# USB.net
KiCad netlist of a schematic drawn in Altium Designer
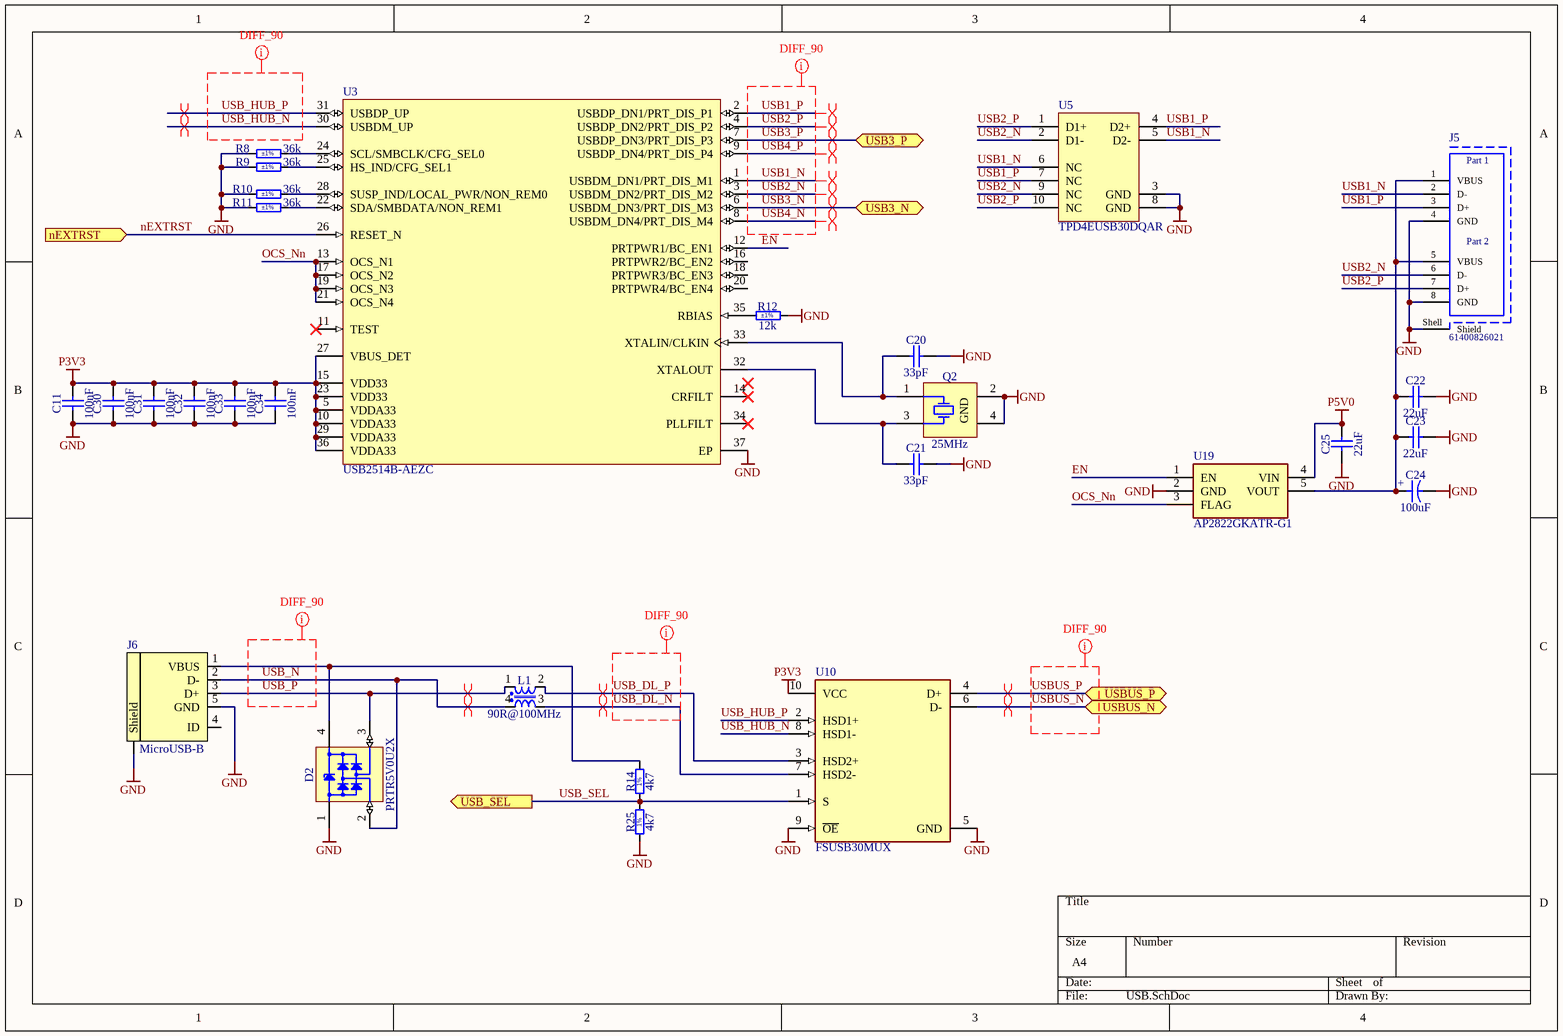
[diagram p0: USB.SchDoc]

(export (version "E")
  (design (tool "Eeschema 10.0.6"))
  (components
    (comp (ref "C11")
      (value "100nF")
      (footprint "CAPC1005X55N")
      (description "Non-polarised capacitor")
      (fields
        (field (name "PART NUMBER") "CC0402_100NF_16V_10%_X5R")
        (field (name "VOLTAGE") "16V")
        (field (name "AUTHOR") "CERN DEM JLC")
      )
      (libsource (lib "Capacitors") (part "Capacitor - non polarized"))
    )
    (comp (ref "C20")
      (value "33pF")
      (footprint "CAPC1005X55N")
      (description "Non-polarised capacitor")
      (fields
        (field (name "PART NUMBER") "CC0402_33PF_50V_5%_C0G")
        (field (name "VOLTAGE") "50V")
        (field (name "AUTHOR") "CERN DEM JLC")
      )
      (libsource (lib "Capacitors") (part "Capacitor - non polarized"))
    )
    (comp (ref "C21")
      (value "33pF")
      (footprint "CAPC1005X55N")
      (description "Non-polarised capacitor")
      (fields
        (field (name "PART NUMBER") "CC0402_33PF_50V_5%_C0G")
        (field (name "VOLTAGE") "50V")
        (field (name "AUTHOR") "CERN DEM JLC")
      )
      (libsource (lib "Capacitors") (part "Capacitor - non polarized"))
    )
    (comp (ref "C22")
      (value "22uF")
      (footprint "CAPC2012X135N")
      (description "Non-polarised capacitor")
      (fields
        (field (name "PART NUMBER") "CC0805_22UF_10V_+80%-20%_Y5V")
        (field (name "VOLTAGE") "10V")
        (field (name "AUTHOR") "CERN DEM JLC")
      )
      (libsource (lib "Capacitors") (part "Capacitor - non polarized"))
    )
    (comp (ref "C23")
      (value "22uF")
      (footprint "CAPC2012X135N")
      (description "Non-polarised capacitor")
      (fields
        (field (name "PART NUMBER") "CC0805_22UF_10V_+80%-20%_Y5V")
        (field (name "VOLTAGE") "10V")
        (field (name "AUTHOR") "CERN DEM JLC")
      )
      (libsource (lib "Capacitors") (part "Capacitor - non polarized"))
    )
    (comp (ref "C24")
      (value "100uF")
      (footprint "CAPMP3216X180N")
      (description "Polarised capacitor")
      (fields
        (field (name "PART NUMBER") "CTE3216-18_100UF_6.3V_20%_ESR0500_AVX_TLJ")
        (field (name "VOLTAGE") "6.3V")
        (field (name "AUTHOR") "CERN DEM JLC")
      )
      (libsource (lib "Capacitors") (part "Capacitor - polarized"))
    )
    (comp (ref "C25")
      (value "22uF")
      (footprint "CAPC2012X135N")
      (description "Non-polarised capacitor")
      (fields
        (field (name "PART NUMBER") "CC0805_22UF_10V_+80%-20%_Y5V")
        (field (name "VOLTAGE") "10V")
        (field (name "AUTHOR") "CERN DEM JLC")
      )
      (libsource (lib "Capacitors") (part "Capacitor - non polarized"))
    )
    (comp (ref "C30")
      (value "100nF")
      (footprint "CAPC1005X55N")
      (description "Non-polarised capacitor")
      (fields
        (field (name "PART NUMBER") "CC0402_100NF_16V_10%_X5R")
        (field (name "VOLTAGE") "16V")
        (field (name "AUTHOR") "CERN DEM JLC")
      )
      (libsource (lib "Capacitors") (part "Capacitor - non polarized"))
    )
    (comp (ref "C31")
      (value "100nF")
      (footprint "CAPC1005X55N")
      (description "Non-polarised capacitor")
      (fields
        (field (name "PART NUMBER") "CC0402_100NF_16V_10%_X5R")
        (field (name "VOLTAGE") "16V")
        (field (name "AUTHOR") "CERN DEM JLC")
      )
      (libsource (lib "Capacitors") (part "Capacitor - non polarized"))
    )
    (comp (ref "C32")
      (value "100nF")
      (footprint "CAPC1005X55N")
      (description "Non-polarised capacitor")
      (fields
        (field (name "PART NUMBER") "CC0402_100NF_16V_10%_X5R")
        (field (name "VOLTAGE") "16V")
        (field (name "AUTHOR") "CERN DEM JLC")
      )
      (libsource (lib "Capacitors") (part "Capacitor - non polarized"))
    )
    (comp (ref "C33")
      (value "100nF")
      (footprint "CAPC1005X55N")
      (description "Non-polarised capacitor")
      (fields
        (field (name "PART NUMBER") "CC0402_100NF_16V_10%_X5R")
        (field (name "VOLTAGE") "16V")
        (field (name "AUTHOR") "CERN DEM JLC")
      )
      (libsource (lib "Capacitors") (part "Capacitor - non polarized"))
    )
    (comp (ref "C34")
      (value "100nF")
      (footprint "CAPC1005X55N")
      (description "Non-polarised capacitor")
      (fields
        (field (name "PART NUMBER") "CC0402_100NF_16V_10%_X5R")
        (field (name "VOLTAGE") "16V")
        (field (name "AUTHOR") "CERN DEM JLC")
      )
      (libsource (lib "Capacitors") (part "Capacitor - non polarized"))
    )
    (comp (ref "D2")
      (value "PRTR5V0U2X")
      (footprint "SOT190P230X110-4N")
      (description "Ultra Low Capacitance Double Rail-to-Rail ESD Protection Diode")
      (fields
        (field (name "VOLTAGE") "5.5V")
        (field (name "MANUFACTURER") "NXP SEMICONDUCTORS")
        (field (name "AUTHOR") "CERN DEM JLC")
      )
      (libsource (lib "ICs And Semiconductors") (part "PRTR5V0U2X"))
    )
    (comp (ref "J5")
      (value "61400826021")
      (footprint "61400826021")
      (description "USB 2.0 Type A Receptacle WR-COM, Stacked Horizontal, THT")
      (fields (field (name "MANUFACTURER") "Wurth Elektronik") (field (name "PUBLISHER") "WurthElektronik"))
      (libsource (lib "Altium Content Vault") (part "WE-USB-8-1SHLD"))
    )
    (comp (ref "J6")
      (value "MicroUSB-B")
      (footprint "USB-Micro-B-RA-SMD-PiP")
      (description "MicroUSB-B-SMT")
      (fields
        (field (name "PART NUMBER") "USB-Micro-B-RA-SMD-PiP")
        (field (name "MANUFACTURER") "Allen Creations Corp.")
        (field (name "PUBLISHER") "Nordic Semiconductor")
      )
      (libsource (lib "pca10028") (part "MiniUSB-AB-SMT"))
    )
    (comp (ref "L1")
      (value "90R@100MHz")
      (footprint "IND_MURATA_DLW21S")
      (description "Inductor Common Mode")
      (fields
        (field (name "PART NUMBER") "IND_MURATA_DLW21SN900SQ2L")
        (field (name "POWER") "330mA")
        (field (name "AUTHOR") "CERN DEM JLC")
      )
      (libsource (lib "Inductors & Transformers") (part "Inductor Common Mode 1Dot-2 4Dot-3"))
    )
    (comp (ref "Q2")
      (value "25MHz")
      (footprint "XTAL_EPSON_TSX-3225")
      (description "Crystal 4 pins 1=XTAL Control 2=GND3=XTAL 4=GND")
      (fields
        (field (name "PART NUMBER") "XTAL_25MHZ_EPSON_TSX-3225 25.0000MF10Z-AC")
        (field (name "MANUFACTURER") "EPSON")
        (field (name "AUTHOR") "CERN DEM JLC")
      )
      (libsource (lib "ICs And Semiconductors") (part "Quartz Crystal 1X 2GND 3X 4GND"))
    )
    (comp (ref "R8")
      (value "36k")
      (footprint "RESC1005X40N")
      (description "Resistor - 1%")
      (fields
        (field (name "TOLERANCE") "±1%")
        (field (name "PART NUMBER") "R0402_36K_1%_0.0625W_100PPM")
        (field (name "POWER") "0.0625W")
        (field (name "AUTHOR") "CERN DEM JLC")
      )
      (libsource (lib "Resistors") (part "Resistor - 1%"))
    )
    (comp (ref "R9")
      (value "36k")
      (footprint "RESC1005X40N")
      (description "Resistor - 1%")
      (fields
        (field (name "TOLERANCE") "±1%")
        (field (name "PART NUMBER") "R0402_36K_1%_0.0625W_100PPM")
        (field (name "POWER") "0.0625W")
        (field (name "AUTHOR") "CERN DEM JLC")
      )
      (libsource (lib "Resistors") (part "Resistor - 1%"))
    )
    (comp (ref "R10")
      (value "36k")
      (footprint "RESC1005X40N")
      (description "Resistor - 1%")
      (fields
        (field (name "TOLERANCE") "±1%")
        (field (name "PART NUMBER") "R0402_36K_1%_0.0625W_100PPM")
        (field (name "POWER") "0.0625W")
        (field (name "AUTHOR") "CERN DEM JLC")
      )
      (libsource (lib "Resistors") (part "Resistor - 1%"))
    )
    (comp (ref "R11")
      (value "36k")
      (footprint "RESC1005X40N")
      (description "Resistor - 1%")
      (fields
        (field (name "TOLERANCE") "±1%")
        (field (name "PART NUMBER") "R0402_36K_1%_0.0625W_100PPM")
        (field (name "POWER") "0.0625W")
        (field (name "AUTHOR") "CERN DEM JLC")
      )
      (libsource (lib "Resistors") (part "Resistor - 1%"))
    )
    (comp (ref "R12")
      (value "12k")
      (footprint "RESC1005X40N")
      (description "Resistor - 1%")
      (fields
        (field (name "TOLERANCE") "±1%")
        (field (name "PART NUMBER") "R0402_12K_1%_0.0625W_100PPM")
        (field (name "POWER") "0.0625W")
        (field (name "AUTHOR") "CERN DEM JLC")
      )
      (libsource (lib "Resistors") (part "Resistor - 1%"))
    )
    (comp (ref "R14")
      (value "4k7")
      (footprint "RESC1005X40N")
      (description "Resistor - 1%")
      (fields
        (field (name "PART NUMBER") "R0402_4K7_1%_0.0625W_100PPM")
        (field (name "POWER") "0.0625W")
        (field (name "AUTHOR") "CERN DEM JLC")
      )
      (libsource (lib "Resistors") (part "Resistor - 1%"))
    )
    (comp (ref "R25")
      (value "4k7")
      (footprint "RESC1005X40N")
      (description "Resistor - 1%")
      (fields
        (field (name "PART NUMBER") "R0402_4K7_1%_0.0625W_100PPM")
        (field (name "POWER") "0.0625W")
        (field (name "AUTHOR") "CERN DEM JLC")
      )
      (libsource (lib "Resistors") (part "Resistor - 1%"))
    )
    (comp (ref "U3")
      (value "USB2514B-AEZC")
      (footprint "MCHP-QFN-36_V")
      (description "USB 2.0 High-Speed Hub Controller, 4 Ports, 3 to 3.6 V, 0 to 85 degC, 36-Pin QFN, RoHS, Tray")
      (fields (field (name "MANUFACTURER") "Microchip"))
      (libsource (lib "Altium Content Vault") (part "MCHP-USB2514B-QFN-36"))
    )
    (comp (ref "U5")
      (value "TPD4EUSB30DQAR")
      (footprint "DQA0010A_V")
      (fields (field (name "MANUFACTURER") "Texas Instruments"))
      (libsource (lib "Altium Content Vault") (part "TI-TPD4EUSB30-SON_DQA-10"))
    )
    (comp (ref "U10")
      (value "FSUSB30MUX")
      (footprint "FP-846AP-IPC_C")
      (description "IC USB SWITCH 2X2 10MSOP")
      (libsource (lib "Altium Content Vault") (part "5ca72592cac3c78d86a160a61081866"))
    )
    (comp (ref "U19")
      (value "AP2822GKATR-G1")
      (footprint "SamacSys:SOT95P282X145-5N")
      (description "Switch")
      (libsource (lib "*") (part "AP2822GKATR-G1"))
    )
  )
  (nets
    (net (code "1") (name "/EN") (class "Default")
      (node (ref "U19") (pin "1") (pinfunction "EN_1") (pintype "passive"))
      (node (ref "U3") (pin "12") (pinfunction "PRTPWR1/BC_EN1_12") (pintype "bidirectional"))
    )
    (net (code "2") (name "/OCS_Nn") (class "Default")
      (node (ref "U19") (pin "3") (pinfunction "FLAG_3") (pintype "passive"))
      (node (ref "U3") (pin "13") (pinfunction "OCS_N1_13") (pintype "input"))
      (node (ref "U3") (pin "17") (pinfunction "OCS_N2_17") (pintype "input"))
      (node (ref "U3") (pin "19") (pinfunction "OCS_N3_19") (pintype "input"))
      (node (ref "U3") (pin "21") (pinfunction "OCS_N4_21") (pintype "input"))
    )
    (net (code "3") (name "/USB1_N") (class "Default")
      (node (ref "J5") (pin "2") (pinfunction "D-_2") (pintype "passive"))
      (node (ref "U3") (pin "1") (pinfunction "USBDM_DN1/PRT_DIS_M1_1") (pintype "bidirectional"))
      (node (ref "U5") (pin "5") (pinfunction "D2-_5") (pintype "passive"))
      (node (ref "U5") (pin "6") (pinfunction "NC_6") (pintype "passive"))
    )
    (net (code "4") (name "/USB1_P") (class "Default")
      (node (ref "J5") (pin "3") (pinfunction "D+_3") (pintype "passive"))
      (node (ref "U3") (pin "2") (pinfunction "USBDP_DN1/PRT_DIS_P1_2") (pintype "bidirectional"))
      (node (ref "U5") (pin "4") (pinfunction "D2+_4") (pintype "passive"))
      (node (ref "U5") (pin "7") (pinfunction "NC_7") (pintype "passive"))
    )
    (net (code "5") (name "/USB2_N") (class "Default")
      (node (ref "J5") (pin "6") (pinfunction "D-_6") (pintype "passive"))
      (node (ref "U3") (pin "3") (pinfunction "USBDM_DN2/PRT_DIS_M2_3") (pintype "bidirectional"))
      (node (ref "U5") (pin "2") (pinfunction "D1-_2") (pintype "passive"))
      (node (ref "U5") (pin "9") (pinfunction "NC_9") (pintype "passive"))
    )
    (net (code "6") (name "/USB2_P") (class "Default")
      (node (ref "J5") (pin "7") (pinfunction "D+_7") (pintype "passive"))
      (node (ref "U3") (pin "4") (pinfunction "USBDP_DN2/PRT_DIS_P2_4") (pintype "bidirectional"))
      (node (ref "U5") (pin "1") (pinfunction "D1+_1") (pintype "passive"))
      (node (ref "U5") (pin "10") (pinfunction "NC_10") (pintype "passive"))
    )
    (net (code "7") (name "/USB3_N") (class "Default")
      (node (ref "U3") (pin "6") (pinfunction "USBDM_DN3/PRT_DIS_M3_6") (pintype "bidirectional"))
    )
    (net (code "8") (name "/USB3_P") (class "Default")
      (node (ref "U3") (pin "7") (pinfunction "USBDP_DN3/PRT_DIS_P3_7") (pintype "bidirectional"))
    )
    (net (code "9") (name "/USB4_N") (class "Default")
      (node (ref "U3") (pin "8") (pinfunction "USBDM_DN4/PRT_DIS_M4_8") (pintype "bidirectional"))
    )
    (net (code "10") (name "/USB4_P") (class "Default")
      (node (ref "U3") (pin "9") (pinfunction "USBDP_DN4/PRT_DIS_P4_9") (pintype "bidirectional"))
    )
    (net (code "11") (name "/USBUS_N") (class "Default")
      (node (ref "U10") (pin "6") (pinfunction "D-_6") (pintype "passive"))
    )
    (net (code "12") (name "/USBUS_P") (class "Default")
      (node (ref "U10") (pin "4") (pinfunction "D+_4") (pintype "passive"))
    )
    (net (code "13") (name "/USB_DL_N") (class "Default")
      (node (ref "L1") (pin "3") (pinfunction "3_3") (pintype "passive"))
      (node (ref "U10") (pin "7") (pinfunction "HSD2-_7") (pintype "input"))
    )
    (net (code "14") (name "/USB_DL_P") (class "Default")
      (node (ref "L1") (pin "2") (pinfunction "2_2") (pintype "passive"))
      (node (ref "U10") (pin "3") (pinfunction "HSD2+_3") (pintype "input"))
    )
    (net (code "15") (name "/USB_HUB_N") (class "Default")
      (node (ref "U10") (pin "8") (pinfunction "HSD1-_8") (pintype "input"))
      (node (ref "U3") (pin "30") (pinfunction "USBDM_UP_30") (pintype "bidirectional"))
    )
    (net (code "16") (name "/USB_HUB_P") (class "Default")
      (node (ref "U10") (pin "2") (pinfunction "HSD1+_2") (pintype "input"))
      (node (ref "U3") (pin "31") (pinfunction "USBDP_UP_31") (pintype "bidirectional"))
    )
    (net (code "17") (name "/USB_N") (class "Default")
      (node (ref "D2") (pin "2") (pinfunction "I/O1_2") (pintype "bidirectional"))
      (node (ref "J6") (pin "2") (pinfunction "D-_2") (pintype "passive"))
      (node (ref "L1") (pin "4") (pinfunction "4_4") (pintype "passive"))
    )
    (net (code "18") (name "/USB_P") (class "Default")
      (node (ref "D2") (pin "3") (pinfunction "I/O2_3") (pintype "bidirectional"))
      (node (ref "J6") (pin "3") (pinfunction "D+_3") (pintype "passive"))
      (node (ref "L1") (pin "1") (pinfunction "1_1") (pintype "passive"))
    )
    (net (code "19") (name "/USB_SEL") (class "Default")
      (node (ref "R14") (pin "1") (pinfunction "1_1") (pintype "passive"))
      (node (ref "R25") (pin "2") (pinfunction "2_2") (pintype "passive"))
      (node (ref "U10") (pin "1") (pinfunction "S_1") (pintype "input"))
    )
    (net (code "20") (name "/nEXTRST") (class "Default")
      (node (ref "U3") (pin "26") (pinfunction "RESET_N_26") (pintype "input"))
    )
    (net (code "21") (name "GND") (class "Default")
      (node (ref "C11") (pin "1") (pinfunction "1_1") (pintype "passive"))
      (node (ref "C20") (pin "2") (pinfunction "2_2") (pintype "passive"))
      (node (ref "C21") (pin "2") (pinfunction "2_2") (pintype "passive"))
      (node (ref "C22") (pin "2") (pinfunction "2_2") (pintype "passive"))
      (node (ref "C23") (pin "2") (pinfunction "2_2") (pintype "passive"))
      (node (ref "C24") (pin "2") (pinfunction "2_2") (pintype "passive"))
      (node (ref "C25") (pin "1") (pinfunction "1_1") (pintype "passive"))
      (node (ref "C30") (pin "1") (pinfunction "1_1") (pintype "passive"))
      (node (ref "C31") (pin "1") (pinfunction "1_1") (pintype "passive"))
      (node (ref "C32") (pin "1") (pinfunction "1_1") (pintype "passive"))
      (node (ref "C33") (pin "1") (pinfunction "1_1") (pintype "passive"))
      (node (ref "C34") (pin "1") (pinfunction "1_1") (pintype "passive"))
      (node (ref "D2") (pin "1") (pinfunction "GND_1") (pintype "power_in"))
      (node (ref "J5") (pin "4") (pinfunction "GND_4") (pintype "passive"))
      (node (ref "J5") (pin "8") (pinfunction "GND_8") (pintype "passive"))
      (node (ref "J5") (pin "Shell") (pinfunction "Shield_Shell") (pintype "passive"))
      (node (ref "J6") (pin "5") (pinfunction "GND_5") (pintype "power_in"))
      (node (ref "J6") (pin "6") (pinfunction "Shield_6") (pintype "power_in"))
      (node (ref "Q2") (pin "2") (pinfunction "GND_2") (pintype "power_in"))
      (node (ref "Q2") (pin "4") (pinfunction "GND_4") (pintype "power_in"))
      (node (ref "R10") (pin "1") (pinfunction "1_1") (pintype "passive"))
      (node (ref "R11") (pin "1") (pinfunction "1_1") (pintype "passive"))
      (node (ref "R12") (pin "2") (pinfunction "2_2") (pintype "passive"))
      (node (ref "R25") (pin "1") (pinfunction "1_1") (pintype "passive"))
      (node (ref "R8") (pin "1") (pinfunction "1_1") (pintype "passive"))
      (node (ref "R9") (pin "1") (pinfunction "1_1") (pintype "passive"))
      (node (ref "U10") (pin "5") (pinfunction "GND_5") (pintype "power_in"))
      (node (ref "U10") (pin "9") (pinfunction "~{OE}_9") (pintype "input"))
      (node (ref "U19") (pin "2") (pinfunction "GND_2") (pintype "passive"))
      (node (ref "U3") (pin "37") (pinfunction "EP_37") (pintype "power_in"))
      (node (ref "U5") (pin "3") (pinfunction "GND_3") (pintype "power_in"))
      (node (ref "U5") (pin "8") (pinfunction "GND_8") (pintype "power_in"))
    )
    (net (code "22") (name "Net-(D2-VCC)") (class "Default")
      (node (ref "D2") (pin "4") (pinfunction "VCC_4") (pintype "power_in"))
      (node (ref "J6") (pin "1") (pinfunction "VBUS_1") (pintype "power_in"))
      (node (ref "R14") (pin "2") (pinfunction "2_2") (pintype "passive"))
    )
    (net (code "23") (name "Net-(U3-HS_IND{slash}CFG_SEL1)") (class "Default")
      (node (ref "R9") (pin "2") (pinfunction "2_2") (pintype "passive"))
      (node (ref "U3") (pin "25") (pinfunction "HS_IND/CFG_SEL1_25") (pintype "bidirectional"))
    )
    (net (code "24") (name "Net-(U3-RBIAS)") (class "Default")
      (node (ref "R12") (pin "1") (pinfunction "1_1") (pintype "passive"))
      (node (ref "U3") (pin "35") (pinfunction "RBIAS_35") (pintype "input"))
    )
    (net (code "25") (name "Net-(U3-SCL{slash}SMBCLK{slash}CFG_SEL0)") (class "Default")
      (node (ref "R8") (pin "2") (pinfunction "2_2") (pintype "passive"))
      (node (ref "U3") (pin "24") (pinfunction "SCL/SMBCLK/CFG_SEL0_24") (pintype "bidirectional"))
    )
    (net (code "26") (name "Net-(U3-SDA{slash}SMBDATA{slash}NON_REM1)") (class "Default")
      (node (ref "R11") (pin "2") (pinfunction "2_2") (pintype "passive"))
      (node (ref "U3") (pin "22") (pinfunction "SDA/SMBDATA/NON_REM1_22") (pintype "bidirectional"))
    )
    (net (code "27") (name "Net-(U3-SUSP_IND{slash}LOCAL_PWR{slash}NON_REM0)") (class "Default")
      (node (ref "R10") (pin "2") (pinfunction "2_2") (pintype "passive"))
      (node (ref "U3") (pin "28") (pinfunction "SUSP_IND/LOCAL_PWR/NON_REM0_28") (pintype "bidirectional"))
    )
    (net (code "28") (name "Net-(U3-XTALIN{slash}CLKIN)") (class "Default")
      (node (ref "C20") (pin "1") (pinfunction "1_1") (pintype "passive"))
      (node (ref "Q2") (pin "1") (pinfunction "X_1") (pintype "passive"))
      (node (ref "U3") (pin "33") (pinfunction "XTALIN/CLKIN_33") (pintype "input"))
    )
    (net (code "29") (name "Net-(U3-XTALOUT)") (class "Default")
      (node (ref "C21") (pin "1") (pinfunction "1_1") (pintype "passive"))
      (node (ref "Q2") (pin "3") (pinfunction "X_3") (pintype "passive"))
      (node (ref "U3") (pin "32") (pinfunction "XTALOUT_32") (pintype "passive"))
    )
    (net (code "30") (name "Net-(U19-VOUT)") (class "Default")
      (node (ref "C22") (pin "1") (pinfunction "1_1") (pintype "passive"))
      (node (ref "C23") (pin "1") (pinfunction "1_1") (pintype "passive"))
      (node (ref "C24") (pin "1") (pinfunction "1_1") (pintype "passive"))
      (node (ref "J5") (pin "1") (pinfunction "VBUS_1") (pintype "passive"))
      (node (ref "J5") (pin "5") (pinfunction "VBUS_5") (pintype "passive"))
      (node (ref "U19") (pin "5") (pinfunction "VOUT_5") (pintype "passive"))
    )
    (net (code "31") (name "P3V3") (class "Default")
      (node (ref "C11") (pin "2") (pinfunction "2_2") (pintype "passive"))
      (node (ref "C30") (pin "2") (pinfunction "2_2") (pintype "passive"))
      (node (ref "C31") (pin "2") (pinfunction "2_2") (pintype "passive"))
      (node (ref "C32") (pin "2") (pinfunction "2_2") (pintype "passive"))
      (node (ref "C33") (pin "2") (pinfunction "2_2") (pintype "passive"))
      (node (ref "C34") (pin "2") (pinfunction "2_2") (pintype "passive"))
      (node (ref "U10") (pin "10") (pinfunction "VCC_10") (pintype "power_in"))
      (node (ref "U3") (pin "10") (pinfunction "VDDA33_10") (pintype "power_in"))
      (node (ref "U3") (pin "15") (pinfunction "VDD33_15") (pintype "power_in"))
      (node (ref "U3") (pin "23") (pinfunction "VDD33_23") (pintype "power_in"))
      (node (ref "U3") (pin "27") (pinfunction "VBUS_DET_27") (pintype "power_in"))
      (node (ref "U3") (pin "29") (pinfunction "VDDA33_29") (pintype "power_in"))
      (node (ref "U3") (pin "36") (pinfunction "VDDA33_36") (pintype "power_in"))
      (node (ref "U3") (pin "5") (pinfunction "VDDA33_5") (pintype "power_in"))
    )
    (net (code "32") (name "P5V0") (class "Default")
      (node (ref "C25") (pin "2") (pinfunction "2_2") (pintype "passive"))
      (node (ref "U19") (pin "4") (pinfunction "VIN_4") (pintype "passive"))
    )
    (net (code "33") (name "unconnected-(J6-ID-Pad4)") (class "Default")
      (node (ref "J6") (pin "4") (pinfunction "ID_4") (pintype "passive"))
    )
    (net (code "34") (name "unconnected-(U3-CRFILT-Pad14)") (class "Default")
      (node (ref "U3") (pin "14") (pinfunction "CRFILT_14") (pintype "passive+no_connect"))
    )
    (net (code "35") (name "unconnected-(U3-PLLFILT-Pad34)") (class "Default")
      (node (ref "U3") (pin "34") (pinfunction "PLLFILT_34") (pintype "passive+no_connect"))
    )
    (net (code "36") (name "unconnected-(U3-PRTPWR2{slash}BC_EN2-Pad16)") (class "Default")
      (node (ref "U3") (pin "16") (pinfunction "PRTPWR2/BC_EN2_16") (pintype "bidirectional"))
    )
    (net (code "37") (name "unconnected-(U3-PRTPWR3{slash}BC_EN3-Pad18)") (class "Default")
      (node (ref "U3") (pin "18") (pinfunction "PRTPWR3/BC_EN3_18") (pintype "bidirectional"))
    )
    (net (code "38") (name "unconnected-(U3-PRTPWR4{slash}BC_EN4-Pad20)") (class "Default")
      (node (ref "U3") (pin "20") (pinfunction "PRTPWR4/BC_EN4_20") (pintype "bidirectional"))
    )
    (net (code "39") (name "unconnected-(U3-TEST-Pad11)") (class "Default")
      (node (ref "U3") (pin "11") (pinfunction "TEST_11") (pintype "input+no_connect"))
    )
  )
)
